# cgd_gio.net
KiCad netlist of a schematic drawn in Altium Designer
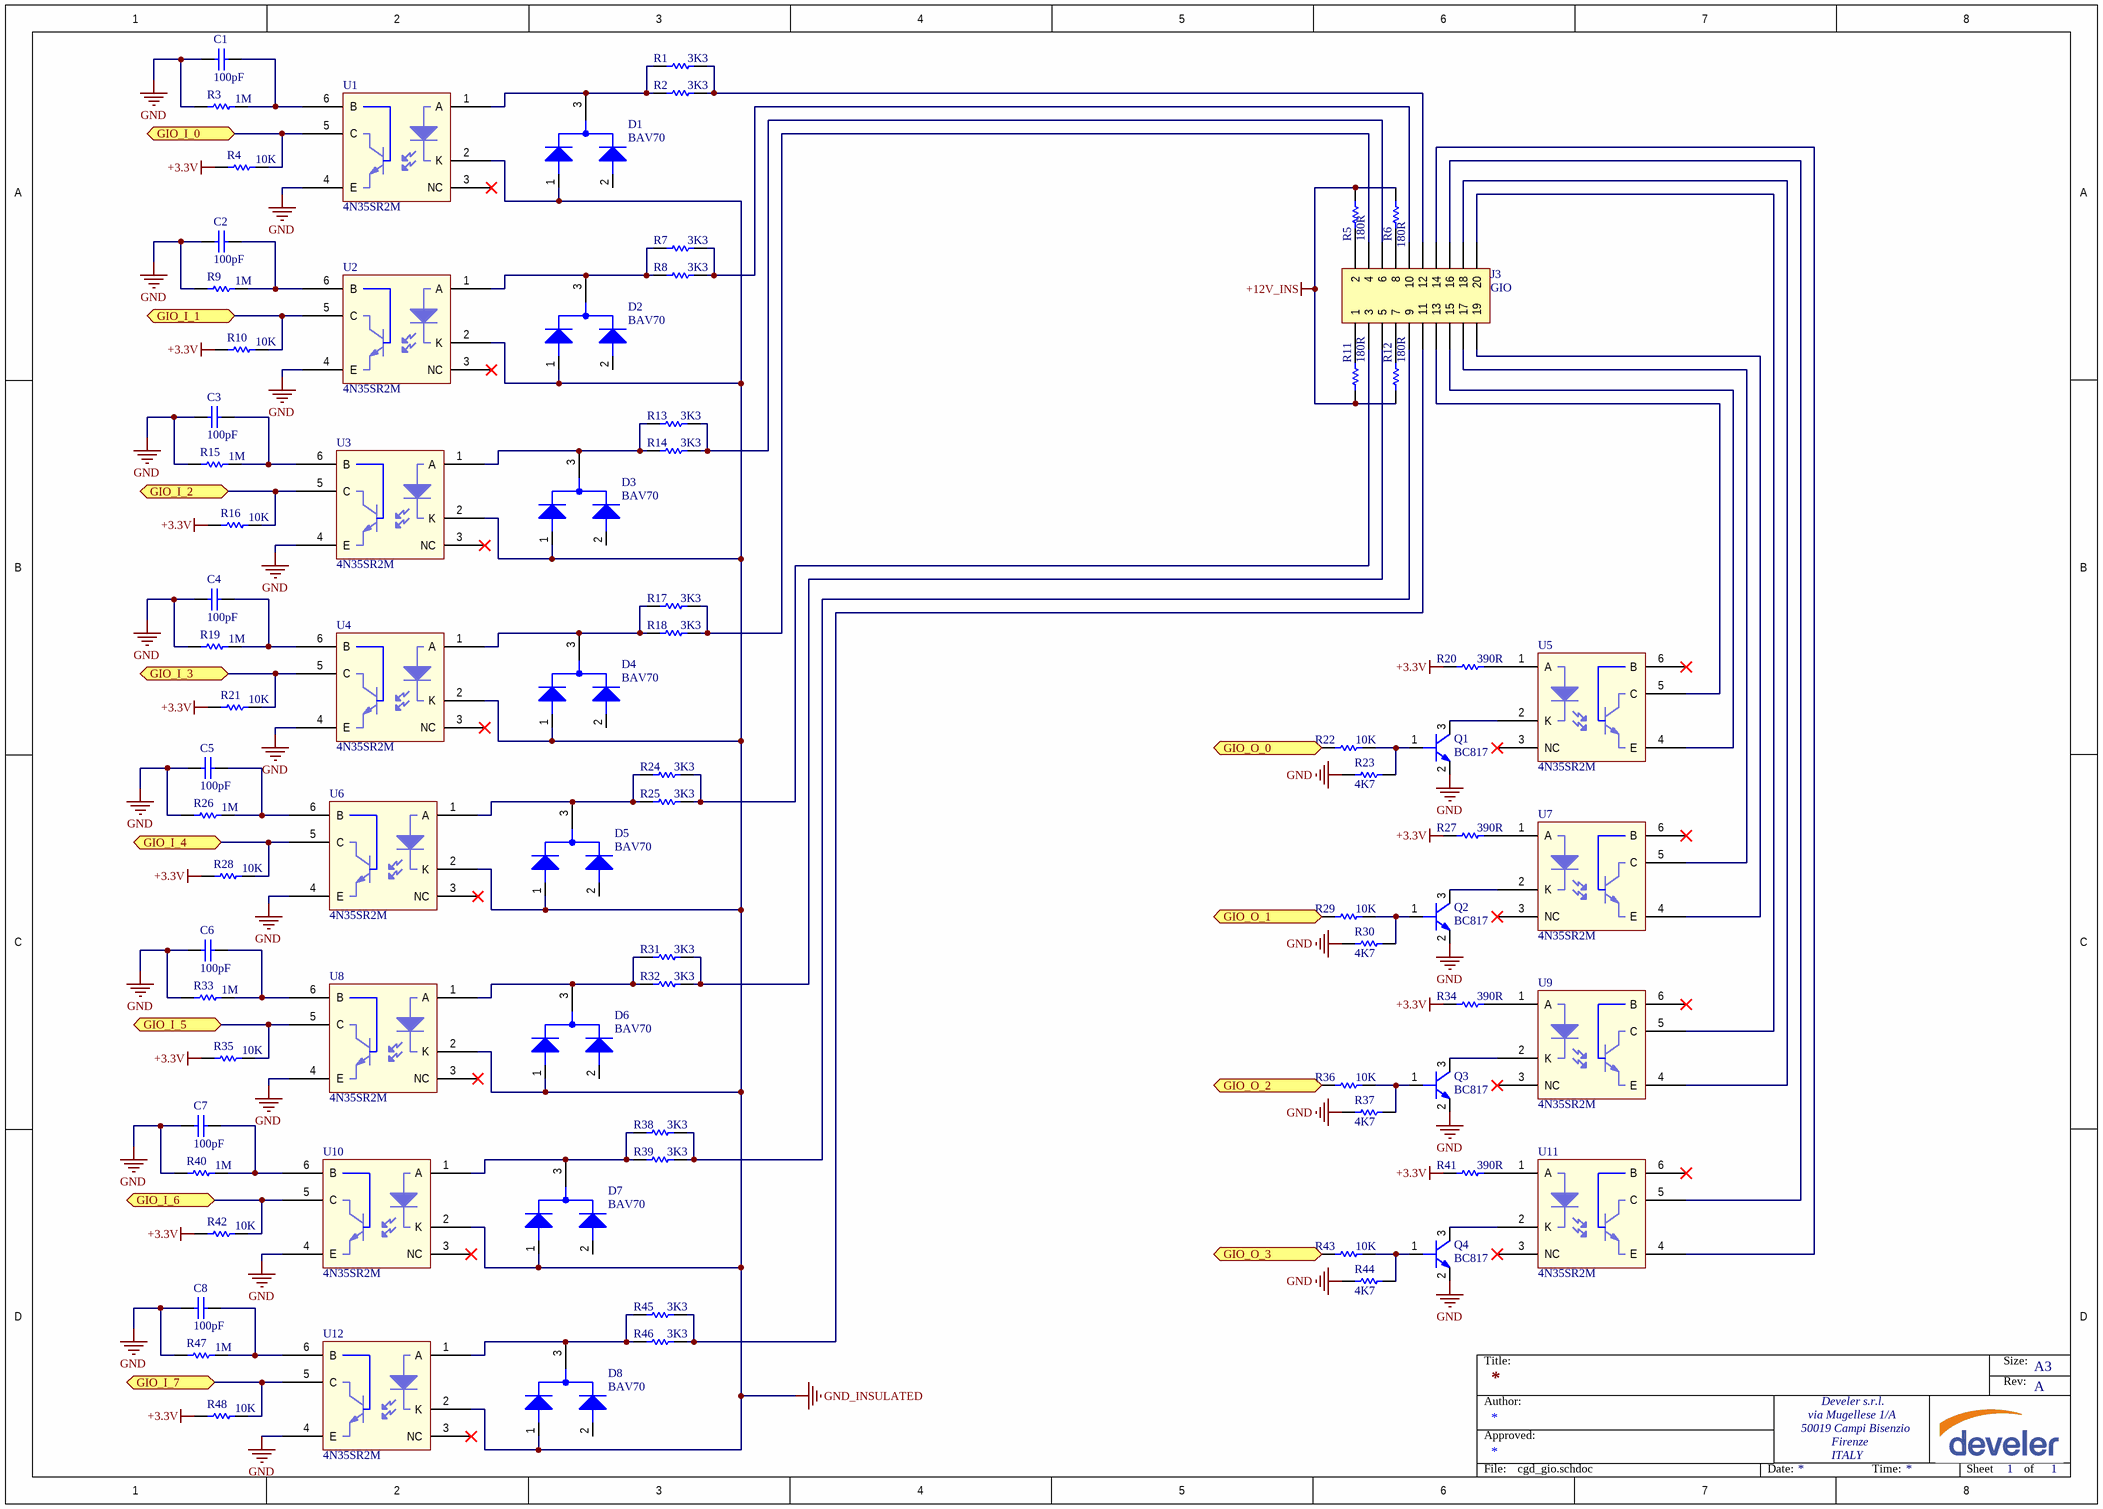
[diagram p0: cgd_gio.schdoc]

(export (version "E")
  (design (tool "Eeschema 10.0.6"))
  (components
    (comp (ref "C1")
      (value "100pF")
      (footprint "0603_[1608]")
      (description "Ceramic COG 50V")
      (fields (field (name "PUBLISHER") "Altium Limited"))
      (libsource (lib "DEVELER_Library") (part "Cap"))
    )
    (comp (ref "C2")
      (value "100pF")
      (footprint "0603_[1608]")
      (description "Ceramic COG 50V")
      (fields (field (name "PUBLISHER") "Altium Limited"))
      (libsource (lib "DEVELER_Library") (part "Cap"))
    )
    (comp (ref "C3")
      (value "100pF")
      (footprint "0603_[1608]")
      (description "Ceramic COG 50V")
      (fields (field (name "PUBLISHER") "Altium Limited"))
      (libsource (lib "DEVELER_Library") (part "Cap"))
    )
    (comp (ref "C4")
      (value "100pF")
      (footprint "0603_[1608]")
      (description "Ceramic COG 50V")
      (fields (field (name "PUBLISHER") "Altium Limited"))
      (libsource (lib "DEVELER_Library") (part "Cap"))
    )
    (comp (ref "C5")
      (value "100pF")
      (footprint "0603_[1608]")
      (description "Ceramic COG 50V")
      (fields (field (name "PUBLISHER") "Altium Limited"))
      (libsource (lib "DEVELER_Library") (part "Cap"))
    )
    (comp (ref "C6")
      (value "100pF")
      (footprint "0603_[1608]")
      (description "Ceramic COG 50V")
      (fields (field (name "PUBLISHER") "Altium Limited"))
      (libsource (lib "DEVELER_Library") (part "Cap"))
    )
    (comp (ref "C7")
      (value "100pF")
      (footprint "0603_[1608]")
      (description "Ceramic COG 50V")
      (fields (field (name "PUBLISHER") "Altium Limited"))
      (libsource (lib "DEVELER_Library") (part "Cap"))
    )
    (comp (ref "C8")
      (value "100pF")
      (footprint "0603_[1608]")
      (description "Ceramic COG 50V")
      (fields (field (name "PUBLISHER") "Altium Limited"))
      (libsource (lib "DEVELER_Library") (part "Cap"))
    )
    (comp (ref "D1")
      (value "BAV70")
      (footprint "SOT-23")
      (description "Diode double")
      (libsource (lib "DEVELER_Library") (part "BAV70"))
    )
    (comp (ref "D2")
      (value "BAV70")
      (footprint "SOT-23")
      (description "Diode double")
      (libsource (lib "DEVELER_Library") (part "BAV70"))
    )
    (comp (ref "D3")
      (value "BAV70")
      (footprint "SOT-23")
      (description "Diode double")
      (libsource (lib "DEVELER_Library") (part "BAV70"))
    )
    (comp (ref "D4")
      (value "BAV70")
      (footprint "SOT-23")
      (description "Diode double")
      (libsource (lib "DEVELER_Library") (part "BAV70"))
    )
    (comp (ref "D5")
      (value "BAV70")
      (footprint "SOT-23")
      (description "Diode double")
      (libsource (lib "DEVELER_Library") (part "BAV70"))
    )
    (comp (ref "D6")
      (value "BAV70")
      (footprint "SOT-23")
      (description "Diode double")
      (libsource (lib "DEVELER_Library") (part "BAV70"))
    )
    (comp (ref "D7")
      (value "BAV70")
      (footprint "SOT-23")
      (description "Diode double")
      (libsource (lib "DEVELER_Library") (part "BAV70"))
    )
    (comp (ref "D8")
      (value "BAV70")
      (footprint "SOT-23")
      (description "Diode double")
      (libsource (lib "DEVELER_Library") (part "BAV70"))
    )
    (comp (ref "J3")
      (value "GIO")
      (footprint "TBLOCK_2X10_3.5MM_HOR_THD_FLANGED")
      (description "Terminal Block 3.5mm Horizontal (Phoenix contact DMC 1,5/10-G1F-3,5-LR P20THR)")
      (fields (field (name "PUBLISHER") "Altium Limited"))
      (libsource (lib "Miscellaneous Connectors") (part "Header 10X2"))
    )
    (comp (ref "Q1")
      (value "BC817")
      (footprint "SOT-23")
      (description "BJT Transistor")
      (libsource (lib "DEVELER_Library") (part "BC817"))
    )
    (comp (ref "Q2")
      (value "BC817")
      (footprint "SOT-23")
      (description "BJT Transistor")
      (libsource (lib "DEVELER_Library") (part "BC817"))
    )
    (comp (ref "Q3")
      (value "BC817")
      (footprint "SOT-23")
      (description "BJT Transistor")
      (libsource (lib "DEVELER_Library") (part "BC817"))
    )
    (comp (ref "Q4")
      (value "BC817")
      (footprint "SOT-23")
      (description "BJT Transistor")
      (libsource (lib "DEVELER_Library") (part "BC817"))
    )
    (comp (ref "R1")
      (value "3K3")
      (footprint "0603_[1608]")
      (description "Resistor")
      (fields (field (name "PUBLISHER") "Altium Limited"))
      (libsource (lib "DEVELER_Library") (part "Res1"))
    )
    (comp (ref "R2")
      (value "3K3")
      (footprint "0603_[1608]")
      (description "Resistor")
      (fields (field (name "PUBLISHER") "Altium Limited"))
      (libsource (lib "DEVELER_Library") (part "Res1"))
    )
    (comp (ref "R3")
      (value "1M")
      (footprint "0603_[1608]")
      (description "Resistor")
      (fields (field (name "PUBLISHER") "Altium Limited"))
      (libsource (lib "DEVELER_Library") (part "Res1"))
    )
    (comp (ref "R4")
      (value "10K")
      (footprint "0603_[1608]")
      (description "Resistor")
      (fields (field (name "PUBLISHER") "Altium Limited"))
      (libsource (lib "DEVELER_Library") (part "Res1"))
    )
    (comp (ref "R5")
      (value "180R")
      (footprint "0603_[1608]")
      (description "Resistor")
      (fields (field (name "PUBLISHER") "Altium Limited"))
      (libsource (lib "DEVELER_Library") (part "Res1"))
    )
    (comp (ref "R6")
      (value "180R")
      (footprint "0603_[1608]")
      (description "Resistor")
      (fields (field (name "PUBLISHER") "Altium Limited"))
      (libsource (lib "DEVELER_Library") (part "Res1"))
    )
    (comp (ref "R7")
      (value "3K3")
      (footprint "0603_[1608]")
      (description "Resistor")
      (fields (field (name "PUBLISHER") "Altium Limited"))
      (libsource (lib "DEVELER_Library") (part "Res1"))
    )
    (comp (ref "R8")
      (value "3K3")
      (footprint "0603_[1608]")
      (description "Resistor")
      (fields (field (name "PUBLISHER") "Altium Limited"))
      (libsource (lib "DEVELER_Library") (part "Res1"))
    )
    (comp (ref "R9")
      (value "1M")
      (footprint "0603_[1608]")
      (description "Resistor")
      (fields (field (name "PUBLISHER") "Altium Limited"))
      (libsource (lib "DEVELER_Library") (part "Res1"))
    )
    (comp (ref "R10")
      (value "10K")
      (footprint "0603_[1608]")
      (description "Resistor")
      (fields (field (name "PUBLISHER") "Altium Limited"))
      (libsource (lib "DEVELER_Library") (part "Res1"))
    )
    (comp (ref "R11")
      (value "180R")
      (footprint "0603_[1608]")
      (description "Resistor")
      (fields (field (name "PUBLISHER") "Altium Limited"))
      (libsource (lib "DEVELER_Library") (part "Res1"))
    )
    (comp (ref "R12")
      (value "180R")
      (footprint "0603_[1608]")
      (description "Resistor")
      (fields (field (name "PUBLISHER") "Altium Limited"))
      (libsource (lib "DEVELER_Library") (part "Res1"))
    )
    (comp (ref "R13")
      (value "3K3")
      (footprint "0603_[1608]")
      (description "Resistor")
      (fields (field (name "PUBLISHER") "Altium Limited"))
      (libsource (lib "DEVELER_Library") (part "Res1"))
    )
    (comp (ref "R14")
      (value "3K3")
      (footprint "0603_[1608]")
      (description "Resistor")
      (fields (field (name "PUBLISHER") "Altium Limited"))
      (libsource (lib "DEVELER_Library") (part "Res1"))
    )
    (comp (ref "R15")
      (value "1M")
      (footprint "0603_[1608]")
      (description "Resistor")
      (fields (field (name "PUBLISHER") "Altium Limited"))
      (libsource (lib "DEVELER_Library") (part "Res1"))
    )
    (comp (ref "R16")
      (value "10K")
      (footprint "0603_[1608]")
      (description "Resistor")
      (fields (field (name "PUBLISHER") "Altium Limited"))
      (libsource (lib "DEVELER_Library") (part "Res1"))
    )
    (comp (ref "R17")
      (value "3K3")
      (footprint "0603_[1608]")
      (description "Resistor")
      (fields (field (name "PUBLISHER") "Altium Limited"))
      (libsource (lib "DEVELER_Library") (part "Res1"))
    )
    (comp (ref "R18")
      (value "3K3")
      (footprint "0603_[1608]")
      (description "Resistor")
      (fields (field (name "PUBLISHER") "Altium Limited"))
      (libsource (lib "DEVELER_Library") (part "Res1"))
    )
    (comp (ref "R19")
      (value "1M")
      (footprint "0603_[1608]")
      (description "Resistor")
      (fields (field (name "PUBLISHER") "Altium Limited"))
      (libsource (lib "DEVELER_Library") (part "Res1"))
    )
    (comp (ref "R20")
      (value "390R")
      (footprint "0603_[1608]")
      (description "Resistor")
      (fields (field (name "PUBLISHER") "Altium Limited"))
      (libsource (lib "DEVELER_Library") (part "Res1"))
    )
    (comp (ref "R21")
      (value "10K")
      (footprint "0603_[1608]")
      (description "Resistor")
      (fields (field (name "PUBLISHER") "Altium Limited"))
      (libsource (lib "DEVELER_Library") (part "Res1"))
    )
    (comp (ref "R22")
      (value "10K")
      (footprint "0603_[1608]")
      (description "Resistor")
      (fields (field (name "PUBLISHER") "Altium Limited"))
      (libsource (lib "DEVELER_Library") (part "Res1"))
    )
    (comp (ref "R23")
      (value "4K7")
      (footprint "0603_[1608]")
      (description "Resistor")
      (fields (field (name "PUBLISHER") "Altium Limited"))
      (libsource (lib "DEVELER_Library") (part "Res1"))
    )
    (comp (ref "R24")
      (value "3K3")
      (footprint "0603_[1608]")
      (description "Resistor")
      (fields (field (name "PUBLISHER") "Altium Limited"))
      (libsource (lib "DEVELER_Library") (part "Res1"))
    )
    (comp (ref "R25")
      (value "3K3")
      (footprint "0603_[1608]")
      (description "Resistor")
      (fields (field (name "PUBLISHER") "Altium Limited"))
      (libsource (lib "DEVELER_Library") (part "Res1"))
    )
    (comp (ref "R26")
      (value "1M")
      (footprint "0603_[1608]")
      (description "Resistor")
      (fields (field (name "PUBLISHER") "Altium Limited"))
      (libsource (lib "DEVELER_Library") (part "Res1"))
    )
    (comp (ref "R27")
      (value "390R")
      (footprint "0603_[1608]")
      (description "Resistor")
      (fields (field (name "PUBLISHER") "Altium Limited"))
      (libsource (lib "DEVELER_Library") (part "Res1"))
    )
    (comp (ref "R28")
      (value "10K")
      (footprint "0603_[1608]")
      (description "Resistor")
      (fields (field (name "PUBLISHER") "Altium Limited"))
      (libsource (lib "DEVELER_Library") (part "Res1"))
    )
    (comp (ref "R29")
      (value "10K")
      (footprint "0603_[1608]")
      (description "Resistor")
      (fields (field (name "PUBLISHER") "Altium Limited"))
      (libsource (lib "DEVELER_Library") (part "Res1"))
    )
    (comp (ref "R30")
      (value "4K7")
      (footprint "0603_[1608]")
      (description "Resistor")
      (fields (field (name "PUBLISHER") "Altium Limited"))
      (libsource (lib "DEVELER_Library") (part "Res1"))
    )
    (comp (ref "R31")
      (value "3K3")
      (footprint "0603_[1608]")
      (description "Resistor")
      (fields (field (name "PUBLISHER") "Altium Limited"))
      (libsource (lib "DEVELER_Library") (part "Res1"))
    )
    (comp (ref "R32")
      (value "3K3")
      (footprint "0603_[1608]")
      (description "Resistor")
      (fields (field (name "PUBLISHER") "Altium Limited"))
      (libsource (lib "DEVELER_Library") (part "Res1"))
    )
    (comp (ref "R33")
      (value "1M")
      (footprint "0603_[1608]")
      (description "Resistor")
      (fields (field (name "PUBLISHER") "Altium Limited"))
      (libsource (lib "DEVELER_Library") (part "Res1"))
    )
    (comp (ref "R34")
      (value "390R")
      (footprint "0603_[1608]")
      (description "Resistor")
      (fields (field (name "PUBLISHER") "Altium Limited"))
      (libsource (lib "DEVELER_Library") (part "Res1"))
    )
    (comp (ref "R35")
      (value "10K")
      (footprint "0603_[1608]")
      (description "Resistor")
      (fields (field (name "PUBLISHER") "Altium Limited"))
      (libsource (lib "DEVELER_Library") (part "Res1"))
    )
    (comp (ref "R36")
      (value "10K")
      (footprint "0603_[1608]")
      (description "Resistor")
      (fields (field (name "PUBLISHER") "Altium Limited"))
      (libsource (lib "DEVELER_Library") (part "Res1"))
    )
    (comp (ref "R37")
      (value "4K7")
      (footprint "0603_[1608]")
      (description "Resistor")
      (fields (field (name "PUBLISHER") "Altium Limited"))
      (libsource (lib "DEVELER_Library") (part "Res1"))
    )
    (comp (ref "R38")
      (value "3K3")
      (footprint "0603_[1608]")
      (description "Resistor")
      (fields (field (name "PUBLISHER") "Altium Limited"))
      (libsource (lib "DEVELER_Library") (part "Res1"))
    )
    (comp (ref "R39")
      (value "3K3")
      (footprint "0603_[1608]")
      (description "Resistor")
      (fields (field (name "PUBLISHER") "Altium Limited"))
      (libsource (lib "DEVELER_Library") (part "Res1"))
    )
    (comp (ref "R40")
      (value "1M")
      (footprint "0603_[1608]")
      (description "Resistor")
      (fields (field (name "PUBLISHER") "Altium Limited"))
      (libsource (lib "DEVELER_Library") (part "Res1"))
    )
    (comp (ref "R41")
      (value "390R")
      (footprint "0603_[1608]")
      (description "Resistor")
      (fields (field (name "PUBLISHER") "Altium Limited"))
      (libsource (lib "DEVELER_Library") (part "Res1"))
    )
    (comp (ref "R42")
      (value "10K")
      (footprint "0603_[1608]")
      (description "Resistor")
      (fields (field (name "PUBLISHER") "Altium Limited"))
      (libsource (lib "DEVELER_Library") (part "Res1"))
    )
    (comp (ref "R43")
      (value "10K")
      (footprint "0603_[1608]")
      (description "Resistor")
      (fields (field (name "PUBLISHER") "Altium Limited"))
      (libsource (lib "DEVELER_Library") (part "Res1"))
    )
    (comp (ref "R44")
      (value "4K7")
      (footprint "0603_[1608]")
      (description "Resistor")
      (fields (field (name "PUBLISHER") "Altium Limited"))
      (libsource (lib "DEVELER_Library") (part "Res1"))
    )
    (comp (ref "R45")
      (value "3K3")
      (footprint "0603_[1608]")
      (description "Resistor")
      (fields (field (name "PUBLISHER") "Altium Limited"))
      (libsource (lib "DEVELER_Library") (part "Res1"))
    )
    (comp (ref "R46")
      (value "3K3")
      (footprint "0603_[1608]")
      (description "Resistor")
      (fields (field (name "PUBLISHER") "Altium Limited"))
      (libsource (lib "DEVELER_Library") (part "Res1"))
    )
    (comp (ref "R47")
      (value "1M")
      (footprint "0603_[1608]")
      (description "Resistor")
      (fields (field (name "PUBLISHER") "Altium Limited"))
      (libsource (lib "DEVELER_Library") (part "Res1"))
    )
    (comp (ref "R48")
      (value "10K")
      (footprint "0603_[1608]")
      (description "Resistor")
      (fields (field (name "PUBLISHER") "Altium Limited"))
      (libsource (lib "DEVELER_Library") (part "Res1"))
    )
    (comp (ref "U1")
      (value "4N35SR2M")
      (footprint "SOIC6_OPTO")
      (description "Optocoupler")
      (libsource (lib "DEVELER_Library") (part "4N2x"))
    )
    (comp (ref "U2")
      (value "4N35SR2M")
      (footprint "SOIC6_OPTO")
      (description "Optocoupler")
      (libsource (lib "DEVELER_Library") (part "4N2x"))
    )
    (comp (ref "U3")
      (value "4N35SR2M")
      (footprint "SOIC6_OPTO")
      (description "Optocoupler")
      (libsource (lib "DEVELER_Library") (part "4N2x"))
    )
    (comp (ref "U4")
      (value "4N35SR2M")
      (footprint "SOIC6_OPTO")
      (description "Optocoupler")
      (libsource (lib "DEVELER_Library") (part "4N2x"))
    )
    (comp (ref "U5")
      (value "4N35SR2M")
      (footprint "SOIC6_OPTO")
      (description "Optocoupler")
      (libsource (lib "") (part "4N2x_1"))
    )
    (comp (ref "U6")
      (value "4N35SR2M")
      (footprint "SOIC6_OPTO")
      (description "Optocoupler")
      (libsource (lib "DEVELER_Library") (part "4N2x"))
    )
    (comp (ref "U7")
      (value "4N35SR2M")
      (footprint "SOIC6_OPTO")
      (description "Optocoupler")
      (libsource (lib "") (part "4N2x_1"))
    )
    (comp (ref "U8")
      (value "4N35SR2M")
      (footprint "SOIC6_OPTO")
      (description "Optocoupler")
      (libsource (lib "DEVELER_Library") (part "4N2x"))
    )
    (comp (ref "U9")
      (value "4N35SR2M")
      (footprint "SOIC6_OPTO")
      (description "Optocoupler")
      (libsource (lib "") (part "4N2x_1"))
    )
    (comp (ref "U10")
      (value "4N35SR2M")
      (footprint "SOIC6_OPTO")
      (description "Optocoupler")
      (libsource (lib "DEVELER_Library") (part "4N2x"))
    )
    (comp (ref "U11")
      (value "4N35SR2M")
      (footprint "SOIC6_OPTO")
      (description "Optocoupler")
      (libsource (lib "") (part "4N2x_1"))
    )
    (comp (ref "U12")
      (value "4N35SR2M")
      (footprint "SOIC6_OPTO")
      (description "Optocoupler")
      (libsource (lib "DEVELER_Library") (part "4N2x"))
    )
  )
  (nets
    (net (code "1") (name "+3.3V") (class "Default")
      (node (ref "R10") (pin "2") (pinfunction "2_2") (pintype "passive"))
      (node (ref "R16") (pin "2") (pinfunction "2_2") (pintype "passive"))
      (node (ref "R20") (pin "2") (pinfunction "2_2") (pintype "passive"))
      (node (ref "R21") (pin "2") (pinfunction "2_2") (pintype "passive"))
      (node (ref "R27") (pin "2") (pinfunction "2_2") (pintype "passive"))
      (node (ref "R28") (pin "2") (pinfunction "2_2") (pintype "passive"))
      (node (ref "R34") (pin "2") (pinfunction "2_2") (pintype "passive"))
      (node (ref "R35") (pin "2") (pinfunction "2_2") (pintype "passive"))
      (node (ref "R4") (pin "2") (pinfunction "2_2") (pintype "passive"))
      (node (ref "R41") (pin "2") (pinfunction "2_2") (pintype "passive"))
      (node (ref "R42") (pin "2") (pinfunction "2_2") (pintype "passive"))
      (node (ref "R48") (pin "2") (pinfunction "2_2") (pintype "passive"))
    )
    (net (code "2") (name "+12V_INS") (class "Default")
      (node (ref "R11") (pin "2") (pinfunction "2_2") (pintype "passive"))
      (node (ref "R12") (pin "2") (pinfunction "2_2") (pintype "passive"))
      (node (ref "R5") (pin "1") (pinfunction "1_1") (pintype "passive"))
      (node (ref "R6") (pin "1") (pinfunction "1_1") (pintype "passive"))
    )
    (net (code "3") (name "/GIO_I_0") (class "Default")
      (node (ref "R4") (pin "1") (pinfunction "1_1") (pintype "passive"))
      (node (ref "U1") (pin "5") (pinfunction "C_5") (pintype "power_in"))
    )
    (net (code "4") (name "/GIO_I_1") (class "Default")
      (node (ref "R10") (pin "1") (pinfunction "1_1") (pintype "passive"))
      (node (ref "U2") (pin "5") (pinfunction "C_5") (pintype "power_in"))
    )
    (net (code "5") (name "/GIO_I_2") (class "Default")
      (node (ref "R16") (pin "1") (pinfunction "1_1") (pintype "passive"))
      (node (ref "U3") (pin "5") (pinfunction "C_5") (pintype "power_in"))
    )
    (net (code "6") (name "/GIO_I_3") (class "Default")
      (node (ref "R21") (pin "1") (pinfunction "1_1") (pintype "passive"))
      (node (ref "U4") (pin "5") (pinfunction "C_5") (pintype "power_in"))
    )
    (net (code "7") (name "/GIO_I_4") (class "Default")
      (node (ref "R28") (pin "1") (pinfunction "1_1") (pintype "passive"))
      (node (ref "U6") (pin "5") (pinfunction "C_5") (pintype "power_in"))
    )
    (net (code "8") (name "/GIO_I_5") (class "Default")
      (node (ref "R35") (pin "1") (pinfunction "1_1") (pintype "passive"))
      (node (ref "U8") (pin "5") (pinfunction "C_5") (pintype "power_in"))
    )
    (net (code "9") (name "/GIO_I_6") (class "Default")
      (node (ref "R42") (pin "1") (pinfunction "1_1") (pintype "passive"))
      (node (ref "U10") (pin "5") (pinfunction "C_5") (pintype "power_in"))
    )
    (net (code "10") (name "/GIO_I_7") (class "Default")
      (node (ref "R48") (pin "1") (pinfunction "1_1") (pintype "passive"))
      (node (ref "U12") (pin "5") (pinfunction "C_5") (pintype "power_in"))
    )
    (net (code "11") (name "/GIO_O_0") (class "Default")
      (node (ref "R22") (pin "2") (pinfunction "2_2") (pintype "passive"))
    )
    (net (code "12") (name "/GIO_O_1") (class "Default")
      (node (ref "R29") (pin "2") (pinfunction "2_2") (pintype "passive"))
    )
    (net (code "13") (name "/GIO_O_2") (class "Default")
      (node (ref "R36") (pin "2") (pinfunction "2_2") (pintype "passive"))
    )
    (net (code "14") (name "/GIO_O_3") (class "Default")
      (node (ref "R43") (pin "2") (pinfunction "2_2") (pintype "passive"))
    )
    (net (code "15") (name "GND") (class "Default")
      (node (ref "C1") (pin "2") (pinfunction "2_2") (pintype "passive"))
      (node (ref "C2") (pin "2") (pinfunction "2_2") (pintype "passive"))
      (node (ref "C3") (pin "2") (pinfunction "2_2") (pintype "passive"))
      (node (ref "C4") (pin "2") (pinfunction "2_2") (pintype "passive"))
      (node (ref "C5") (pin "2") (pinfunction "2_2") (pintype "passive"))
      (node (ref "C6") (pin "2") (pinfunction "2_2") (pintype "passive"))
      (node (ref "C7") (pin "2") (pinfunction "2_2") (pintype "passive"))
      (node (ref "C8") (pin "2") (pinfunction "2_2") (pintype "passive"))
      (node (ref "Q1") (pin "2") (pinfunction "E_2") (pintype "passive"))
      (node (ref "Q2") (pin "2") (pinfunction "E_2") (pintype "passive"))
      (node (ref "Q3") (pin "2") (pinfunction "E_2") (pintype "passive"))
      (node (ref "Q4") (pin "2") (pinfunction "E_2") (pintype "passive"))
      (node (ref "R15") (pin "2") (pinfunction "2_2") (pintype "passive"))
      (node (ref "R19") (pin "2") (pinfunction "2_2") (pintype "passive"))
      (node (ref "R23") (pin "1") (pinfunction "1_1") (pintype "passive"))
      (node (ref "R26") (pin "2") (pinfunction "2_2") (pintype "passive"))
      (node (ref "R3") (pin "2") (pinfunction "2_2") (pintype "passive"))
      (node (ref "R30") (pin "1") (pinfunction "1_1") (pintype "passive"))
      (node (ref "R33") (pin "2") (pinfunction "2_2") (pintype "passive"))
      (node (ref "R37") (pin "1") (pinfunction "1_1") (pintype "passive"))
      (node (ref "R40") (pin "2") (pinfunction "2_2") (pintype "passive"))
      (node (ref "R44") (pin "1") (pinfunction "1_1") (pintype "passive"))
      (node (ref "R47") (pin "2") (pinfunction "2_2") (pintype "passive"))
      (node (ref "R9") (pin "2") (pinfunction "2_2") (pintype "passive"))
      (node (ref "U1") (pin "4") (pinfunction "E_4") (pintype "power_in"))
      (node (ref "U10") (pin "4") (pinfunction "E_4") (pintype "power_in"))
      (node (ref "U12") (pin "4") (pinfunction "E_4") (pintype "power_in"))
      (node (ref "U2") (pin "4") (pinfunction "E_4") (pintype "power_in"))
      (node (ref "U3") (pin "4") (pinfunction "E_4") (pintype "power_in"))
      (node (ref "U4") (pin "4") (pinfunction "E_4") (pintype "power_in"))
      (node (ref "U6") (pin "4") (pinfunction "E_4") (pintype "power_in"))
      (node (ref "U8") (pin "4") (pinfunction "E_4") (pintype "power_in"))
    )
    (net (code "16") (name "GND_INSULATED") (class "Default")
      (node (ref "D1") (pin "1") (pinfunction "1_1") (pintype "passive"))
      (node (ref "D2") (pin "1") (pinfunction "1_1") (pintype "passive"))
      (node (ref "D3") (pin "1") (pinfunction "1_1") (pintype "passive"))
      (node (ref "D4") (pin "1") (pinfunction "1_1") (pintype "passive"))
      (node (ref "D5") (pin "1") (pinfunction "1_1") (pintype "passive"))
      (node (ref "D6") (pin "1") (pinfunction "1_1") (pintype "passive"))
      (node (ref "D7") (pin "1") (pinfunction "1_1") (pintype "passive"))
      (node (ref "D8") (pin "1") (pinfunction "1_1") (pintype "passive"))
      (node (ref "U1") (pin "2") (pinfunction "K_2") (pintype "power_in"))
      (node (ref "U10") (pin "2") (pinfunction "K_2") (pintype "power_in"))
      (node (ref "U12") (pin "2") (pinfunction "K_2") (pintype "power_in"))
      (node (ref "U2") (pin "2") (pinfunction "K_2") (pintype "power_in"))
      (node (ref "U3") (pin "2") (pinfunction "K_2") (pintype "power_in"))
      (node (ref "U4") (pin "2") (pinfunction "K_2") (pintype "power_in"))
      (node (ref "U6") (pin "2") (pinfunction "K_2") (pintype "power_in"))
      (node (ref "U8") (pin "2") (pinfunction "K_2") (pintype "power_in"))
    )
    (net (code "17") (name "Net-(J3-Pad1)") (class "Default")
      (node (ref "J3") (pin "1") (pinfunction "1_1") (pintype "passive"))
      (node (ref "R11") (pin "1") (pinfunction "1_1") (pintype "passive"))
    )
    (net (code "18") (name "Net-(J3-Pad2)") (class "Default")
      (node (ref "J3") (pin "2") (pinfunction "2_2") (pintype "passive"))
      (node (ref "R5") (pin "2") (pinfunction "2_2") (pintype "passive"))
    )
    (net (code "19") (name "Net-(J3-Pad3)") (class "Default")
      (node (ref "J3") (pin "3") (pinfunction "3_3") (pintype "passive"))
      (node (ref "R24") (pin "2") (pinfunction "2_2") (pintype "passive"))
      (node (ref "R25") (pin "2") (pinfunction "2_2") (pintype "passive"))
    )
    (net (code "20") (name "Net-(J3-Pad4)") (class "Default")
      (node (ref "J3") (pin "4") (pinfunction "4_4") (pintype "passive"))
      (node (ref "R17") (pin "2") (pinfunction "2_2") (pintype "passive"))
      (node (ref "R18") (pin "2") (pinfunction "2_2") (pintype "passive"))
    )
    (net (code "21") (name "Net-(J3-Pad5)") (class "Default")
      (node (ref "J3") (pin "5") (pinfunction "5_5") (pintype "passive"))
      (node (ref "R31") (pin "2") (pinfunction "2_2") (pintype "passive"))
      (node (ref "R32") (pin "2") (pinfunction "2_2") (pintype "passive"))
    )
    (net (code "22") (name "Net-(J3-Pad6)") (class "Default")
      (node (ref "J3") (pin "6") (pinfunction "6_6") (pintype "passive"))
      (node (ref "R13") (pin "2") (pinfunction "2_2") (pintype "passive"))
      (node (ref "R14") (pin "2") (pinfunction "2_2") (pintype "passive"))
    )
    (net (code "23") (name "Net-(J3-Pad7)") (class "Default")
      (node (ref "J3") (pin "7") (pinfunction "7_7") (pintype "passive"))
      (node (ref "R12") (pin "1") (pinfunction "1_1") (pintype "passive"))
    )
    (net (code "24") (name "Net-(J3-Pad8)") (class "Default")
      (node (ref "J3") (pin "8") (pinfunction "8_8") (pintype "passive"))
      (node (ref "R6") (pin "2") (pinfunction "2_2") (pintype "passive"))
    )
    (net (code "25") (name "Net-(J3-Pad9)") (class "Default")
      (node (ref "J3") (pin "9") (pinfunction "9_9") (pintype "passive"))
      (node (ref "R38") (pin "2") (pinfunction "2_2") (pintype "passive"))
      (node (ref "R39") (pin "2") (pinfunction "2_2") (pintype "passive"))
    )
    (net (code "26") (name "Net-(J3-Pad10)") (class "Default")
      (node (ref "J3") (pin "10") (pinfunction "10_10") (pintype "passive"))
      (node (ref "R7") (pin "2") (pinfunction "2_2") (pintype "passive"))
      (node (ref "R8") (pin "2") (pinfunction "2_2") (pintype "passive"))
    )
    (net (code "27") (name "Net-(J3-Pad11)") (class "Default")
      (node (ref "J3") (pin "11") (pinfunction "11_11") (pintype "passive"))
      (node (ref "R45") (pin "2") (pinfunction "2_2") (pintype "passive"))
      (node (ref "R46") (pin "2") (pinfunction "2_2") (pintype "passive"))
    )
    (net (code "28") (name "Net-(J3-Pad12)") (class "Default")
      (node (ref "J3") (pin "12") (pinfunction "12_12") (pintype "passive"))
      (node (ref "R1") (pin "2") (pinfunction "2_2") (pintype "passive"))
      (node (ref "R2") (pin "2") (pinfunction "2_2") (pintype "passive"))
    )
    (net (code "29") (name "Net-(Q1-B)") (class "Default")
      (node (ref "Q1") (pin "1") (pinfunction "B_1") (pintype "passive"))
      (node (ref "R22") (pin "1") (pinfunction "1_1") (pintype "passive"))
      (node (ref "R23") (pin "2") (pinfunction "2_2") (pintype "passive"))
    )
    (net (code "30") (name "Net-(Q1-C)") (class "Default")
      (node (ref "Q1") (pin "3") (pinfunction "C_3") (pintype "passive"))
      (node (ref "U5") (pin "2") (pinfunction "K_2") (pintype "power_in"))
    )
    (net (code "31") (name "Net-(Q2-B)") (class "Default")
      (node (ref "Q2") (pin "1") (pinfunction "B_1") (pintype "passive"))
      (node (ref "R29") (pin "1") (pinfunction "1_1") (pintype "passive"))
      (node (ref "R30") (pin "2") (pinfunction "2_2") (pintype "passive"))
    )
    (net (code "32") (name "Net-(Q2-C)") (class "Default")
      (node (ref "Q2") (pin "3") (pinfunction "C_3") (pintype "passive"))
      (node (ref "U7") (pin "2") (pinfunction "K_2") (pintype "power_in"))
    )
    (net (code "33") (name "Net-(Q3-B)") (class "Default")
      (node (ref "Q3") (pin "1") (pinfunction "B_1") (pintype "passive"))
      (node (ref "R36") (pin "1") (pinfunction "1_1") (pintype "passive"))
      (node (ref "R37") (pin "2") (pinfunction "2_2") (pintype "passive"))
    )
    (net (code "34") (name "Net-(Q3-C)") (class "Default")
      (node (ref "Q3") (pin "3") (pinfunction "C_3") (pintype "passive"))
      (node (ref "U9") (pin "2") (pinfunction "K_2") (pintype "power_in"))
    )
    (net (code "35") (name "Net-(Q4-B)") (class "Default")
      (node (ref "Q4") (pin "1") (pinfunction "B_1") (pintype "passive"))
      (node (ref "R43") (pin "1") (pinfunction "1_1") (pintype "passive"))
      (node (ref "R44") (pin "2") (pinfunction "2_2") (pintype "passive"))
    )
    (net (code "36") (name "Net-(Q4-C)") (class "Default")
      (node (ref "Q4") (pin "3") (pinfunction "C_3") (pintype "passive"))
      (node (ref "U11") (pin "2") (pinfunction "K_2") (pintype "power_in"))
    )
    (net (code "37") (name "Net-(U1-A)") (class "Default")
      (node (ref "D1") (pin "3") (pinfunction "3_3") (pintype "passive"))
      (node (ref "R1") (pin "1") (pinfunction "1_1") (pintype "passive"))
      (node (ref "R2") (pin "1") (pinfunction "1_1") (pintype "passive"))
      (node (ref "U1") (pin "1") (pinfunction "A_1") (pintype "power_in"))
    )
    (net (code "38") (name "Net-(U1-B)") (class "Default")
      (node (ref "C1") (pin "1") (pinfunction "1_1") (pintype "passive"))
      (node (ref "R3") (pin "1") (pinfunction "1_1") (pintype "passive"))
      (node (ref "U1") (pin "6") (pinfunction "B_6") (pintype "power_in"))
    )
    (net (code "39") (name "Net-(U2-A)") (class "Default")
      (node (ref "D2") (pin "3") (pinfunction "3_3") (pintype "passive"))
      (node (ref "R7") (pin "1") (pinfunction "1_1") (pintype "passive"))
      (node (ref "R8") (pin "1") (pinfunction "1_1") (pintype "passive"))
      (node (ref "U2") (pin "1") (pinfunction "A_1") (pintype "power_in"))
    )
    (net (code "40") (name "Net-(U2-B)") (class "Default")
      (node (ref "C2") (pin "1") (pinfunction "1_1") (pintype "passive"))
      (node (ref "R9") (pin "1") (pinfunction "1_1") (pintype "passive"))
      (node (ref "U2") (pin "6") (pinfunction "B_6") (pintype "power_in"))
    )
    (net (code "41") (name "Net-(U3-A)") (class "Default")
      (node (ref "D3") (pin "3") (pinfunction "3_3") (pintype "passive"))
      (node (ref "R13") (pin "1") (pinfunction "1_1") (pintype "passive"))
      (node (ref "R14") (pin "1") (pinfunction "1_1") (pintype "passive"))
      (node (ref "U3") (pin "1") (pinfunction "A_1") (pintype "power_in"))
    )
    (net (code "42") (name "Net-(U3-B)") (class "Default")
      (node (ref "C3") (pin "1") (pinfunction "1_1") (pintype "passive"))
      (node (ref "R15") (pin "1") (pinfunction "1_1") (pintype "passive"))
      (node (ref "U3") (pin "6") (pinfunction "B_6") (pintype "power_in"))
    )
    (net (code "43") (name "Net-(U4-A)") (class "Default")
      (node (ref "D4") (pin "3") (pinfunction "3_3") (pintype "passive"))
      (node (ref "R17") (pin "1") (pinfunction "1_1") (pintype "passive"))
      (node (ref "R18") (pin "1") (pinfunction "1_1") (pintype "passive"))
      (node (ref "U4") (pin "1") (pinfunction "A_1") (pintype "power_in"))
    )
    (net (code "44") (name "Net-(U4-B)") (class "Default")
      (node (ref "C4") (pin "1") (pinfunction "1_1") (pintype "passive"))
      (node (ref "R19") (pin "1") (pinfunction "1_1") (pintype "passive"))
      (node (ref "U4") (pin "6") (pinfunction "B_6") (pintype "power_in"))
    )
    (net (code "45") (name "Net-(U5-A)") (class "Default")
      (node (ref "R20") (pin "1") (pinfunction "1_1") (pintype "passive"))
      (node (ref "U5") (pin "1") (pinfunction "A_1") (pintype "power_in"))
    )
    (net (code "46") (name "Net-(U5-C)") (class "Default")
      (node (ref "J3") (pin "13") (pinfunction "13_13") (pintype "passive"))
      (node (ref "U5") (pin "5") (pinfunction "C_5") (pintype "power_in"))
    )
    (net (code "47") (name "Net-(U5-E)") (class "Default")
      (node (ref "J3") (pin "15") (pinfunction "15_15") (pintype "passive"))
      (node (ref "U5") (pin "4") (pinfunction "E_4") (pintype "power_in"))
    )
    (net (code "48") (name "Net-(U6-A)") (class "Default")
      (node (ref "D5") (pin "3") (pinfunction "3_3") (pintype "passive"))
      (node (ref "R24") (pin "1") (pinfunction "1_1") (pintype "passive"))
      (node (ref "R25") (pin "1") (pinfunction "1_1") (pintype "passive"))
      (node (ref "U6") (pin "1") (pinfunction "A_1") (pintype "power_in"))
    )
    (net (code "49") (name "Net-(U6-B)") (class "Default")
      (node (ref "C5") (pin "1") (pinfunction "1_1") (pintype "passive"))
      (node (ref "R26") (pin "1") (pinfunction "1_1") (pintype "passive"))
      (node (ref "U6") (pin "6") (pinfunction "B_6") (pintype "power_in"))
    )
    (net (code "50") (name "Net-(U7-A)") (class "Default")
      (node (ref "R27") (pin "1") (pinfunction "1_1") (pintype "passive"))
      (node (ref "U7") (pin "1") (pinfunction "A_1") (pintype "power_in"))
    )
    (net (code "51") (name "Net-(U7-C)") (class "Default")
      (node (ref "J3") (pin "17") (pinfunction "17_17") (pintype "passive"))
      (node (ref "U7") (pin "5") (pinfunction "C_5") (pintype "power_in"))
    )
    (net (code "52") (name "Net-(U7-E)") (class "Default")
      (node (ref "J3") (pin "19") (pinfunction "19_19") (pintype "passive"))
      (node (ref "U7") (pin "4") (pinfunction "E_4") (pintype "power_in"))
    )
    (net (code "53") (name "Net-(U8-A)") (class "Default")
      (node (ref "D6") (pin "3") (pinfunction "3_3") (pintype "passive"))
      (node (ref "R31") (pin "1") (pinfunction "1_1") (pintype "passive"))
      (node (ref "R32") (pin "1") (pinfunction "1_1") (pintype "passive"))
      (node (ref "U8") (pin "1") (pinfunction "A_1") (pintype "power_in"))
    )
    (net (code "54") (name "Net-(U8-B)") (class "Default")
      (node (ref "C6") (pin "1") (pinfunction "1_1") (pintype "passive"))
      (node (ref "R33") (pin "1") (pinfunction "1_1") (pintype "passive"))
      (node (ref "U8") (pin "6") (pinfunction "B_6") (pintype "power_in"))
    )
    (net (code "55") (name "Net-(U9-A)") (class "Default")
      (node (ref "R34") (pin "1") (pinfunction "1_1") (pintype "passive"))
      (node (ref "U9") (pin "1") (pinfunction "A_1") (pintype "power_in"))
    )
    (net (code "56") (name "Net-(U9-C)") (class "Default")
      (node (ref "J3") (pin "20") (pinfunction "20_20") (pintype "passive"))
      (node (ref "U9") (pin "5") (pinfunction "C_5") (pintype "power_in"))
    )
    (net (code "57") (name "Net-(U9-E)") (class "Default")
      (node (ref "J3") (pin "18") (pinfunction "18_18") (pintype "passive"))
      (node (ref "U9") (pin "4") (pinfunction "E_4") (pintype "power_in"))
    )
    (net (code "58") (name "Net-(U10-A)") (class "Default")
      (node (ref "D7") (pin "3") (pinfunction "3_3") (pintype "passive"))
      (node (ref "R38") (pin "1") (pinfunction "1_1") (pintype "passive"))
      (node (ref "R39") (pin "1") (pinfunction "1_1") (pintype "passive"))
      (node (ref "U10") (pin "1") (pinfunction "A_1") (pintype "power_in"))
    )
    (net (code "59") (name "Net-(U10-B)") (class "Default")
      (node (ref "C7") (pin "1") (pinfunction "1_1") (pintype "passive"))
      (node (ref "R40") (pin "1") (pinfunction "1_1") (pintype "passive"))
      (node (ref "U10") (pin "6") (pinfunction "B_6") (pintype "power_in"))
    )
    (net (code "60") (name "Net-(U11-A)") (class "Default")
      (node (ref "R41") (pin "1") (pinfunction "1_1") (pintype "passive"))
      (node (ref "U11") (pin "1") (pinfunction "A_1") (pintype "power_in"))
    )
    (net (code "61") (name "Net-(U11-C)") (class "Default")
      (node (ref "J3") (pin "16") (pinfunction "16_16") (pintype "passive"))
      (node (ref "U11") (pin "5") (pinfunction "C_5") (pintype "power_in"))
    )
    (net (code "62") (name "Net-(U11-E)") (class "Default")
      (node (ref "J3") (pin "14") (pinfunction "14_14") (pintype "passive"))
      (node (ref "U11") (pin "4") (pinfunction "E_4") (pintype "power_in"))
    )
    (net (code "63") (name "Net-(U12-A)") (class "Default")
      (node (ref "D8") (pin "3") (pinfunction "3_3") (pintype "passive"))
      (node (ref "R45") (pin "1") (pinfunction "1_1") (pintype "passive"))
      (node (ref "R46") (pin "1") (pinfunction "1_1") (pintype "passive"))
      (node (ref "U12") (pin "1") (pinfunction "A_1") (pintype "power_in"))
    )
    (net (code "64") (name "Net-(U12-B)") (class "Default")
      (node (ref "C8") (pin "1") (pinfunction "1_1") (pintype "passive"))
      (node (ref "R47") (pin "1") (pinfunction "1_1") (pintype "passive"))
      (node (ref "U12") (pin "6") (pinfunction "B_6") (pintype "power_in"))
    )
    (net (code "65") (name "unconnected-(D1-Pad2)") (class "Default")
      (node (ref "D1") (pin "2") (pinfunction "2_2") (pintype "passive"))
    )
    (net (code "66") (name "unconnected-(D2-Pad2)") (class "Default")
      (node (ref "D2") (pin "2") (pinfunction "2_2") (pintype "passive"))
    )
    (net (code "67") (name "unconnected-(D3-Pad2)") (class "Default")
      (node (ref "D3") (pin "2") (pinfunction "2_2") (pintype "passive"))
    )
    (net (code "68") (name "unconnected-(D4-Pad2)") (class "Default")
      (node (ref "D4") (pin "2") (pinfunction "2_2") (pintype "passive"))
    )
    (net (code "69") (name "unconnected-(D5-Pad2)") (class "Default")
      (node (ref "D5") (pin "2") (pinfunction "2_2") (pintype "passive"))
    )
    (net (code "70") (name "unconnected-(D6-Pad2)") (class "Default")
      (node (ref "D6") (pin "2") (pinfunction "2_2") (pintype "passive"))
    )
    (net (code "71") (name "unconnected-(D7-Pad2)") (class "Default")
      (node (ref "D7") (pin "2") (pinfunction "2_2") (pintype "passive"))
    )
    (net (code "72") (name "unconnected-(D8-Pad2)") (class "Default")
      (node (ref "D8") (pin "2") (pinfunction "2_2") (pintype "passive"))
    )
    (net (code "73") (name "unconnected-(U1-NC-Pad3)") (class "Default")
      (node (ref "U1") (pin "3") (pinfunction "NC_3") (pintype "power_in+no_connect"))
    )
    (net (code "74") (name "unconnected-(U2-NC-Pad3)") (class "Default")
      (node (ref "U2") (pin "3") (pinfunction "NC_3") (pintype "power_in+no_connect"))
    )
    (net (code "75") (name "unconnected-(U3-NC-Pad3)") (class "Default")
      (node (ref "U3") (pin "3") (pinfunction "NC_3") (pintype "power_in+no_connect"))
    )
    (net (code "76") (name "unconnected-(U4-NC-Pad3)") (class "Default")
      (node (ref "U4") (pin "3") (pinfunction "NC_3") (pintype "power_in+no_connect"))
    )
    (net (code "77") (name "unconnected-(U5-B-Pad6)") (class "Default")
      (node (ref "U5") (pin "6") (pinfunction "B_6") (pintype "power_in+no_connect"))
    )
    (net (code "78") (name "unconnected-(U5-NC-Pad3)") (class "Default")
      (node (ref "U5") (pin "3") (pinfunction "NC_3") (pintype "power_in+no_connect"))
    )
    (net (code "79") (name "unconnected-(U6-NC-Pad3)") (class "Default")
      (node (ref "U6") (pin "3") (pinfunction "NC_3") (pintype "power_in+no_connect"))
    )
    (net (code "80") (name "unconnected-(U7-B-Pad6)") (class "Default")
      (node (ref "U7") (pin "6") (pinfunction "B_6") (pintype "power_in+no_connect"))
    )
    (net (code "81") (name "unconnected-(U7-NC-Pad3)") (class "Default")
      (node (ref "U7") (pin "3") (pinfunction "NC_3") (pintype "power_in+no_connect"))
    )
    (net (code "82") (name "unconnected-(U8-NC-Pad3)") (class "Default")
      (node (ref "U8") (pin "3") (pinfunction "NC_3") (pintype "power_in+no_connect"))
    )
    (net (code "83") (name "unconnected-(U9-B-Pad6)") (class "Default")
      (node (ref "U9") (pin "6") (pinfunction "B_6") (pintype "power_in+no_connect"))
    )
    (net (code "84") (name "unconnected-(U9-NC-Pad3)") (class "Default")
      (node (ref "U9") (pin "3") (pinfunction "NC_3") (pintype "power_in+no_connect"))
    )
    (net (code "85") (name "unconnected-(U10-NC-Pad3)") (class "Default")
      (node (ref "U10") (pin "3") (pinfunction "NC_3") (pintype "power_in+no_connect"))
    )
    (net (code "86") (name "unconnected-(U11-B-Pad6)") (class "Default")
      (node (ref "U11") (pin "6") (pinfunction "B_6") (pintype "power_in+no_connect"))
    )
    (net (code "87") (name "unconnected-(U11-NC-Pad3)") (class "Default")
      (node (ref "U11") (pin "3") (pinfunction "NC_3") (pintype "power_in+no_connect"))
    )
    (net (code "88") (name "unconnected-(U12-NC-Pad3)") (class "Default")
      (node (ref "U12") (pin "3") (pinfunction "NC_3") (pintype "power_in+no_connect"))
    )
  )
)
